# Power_MPU.net
KiCad netlist of a schematic drawn in Altium Designer
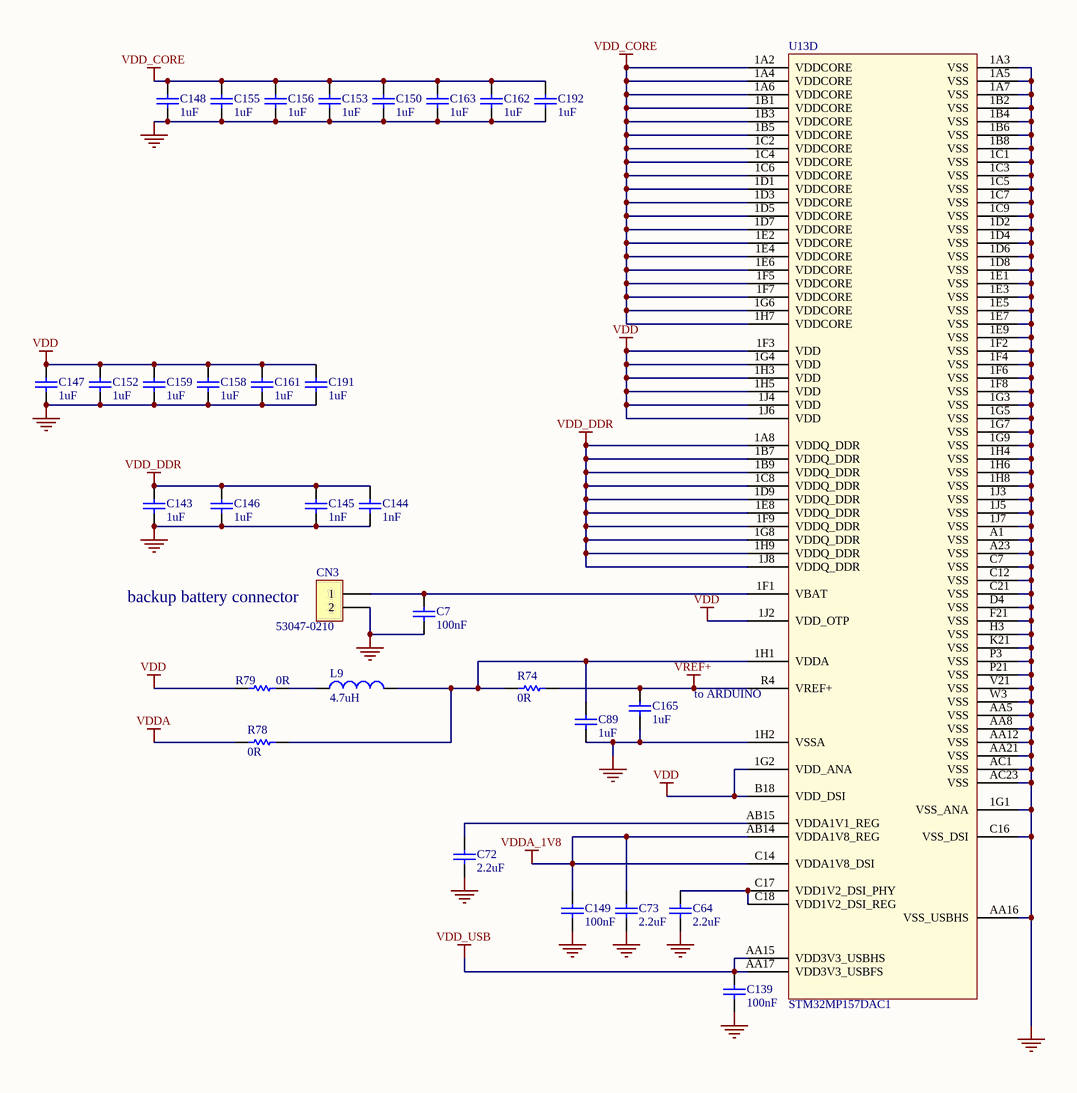
[diagram p0: Power_MPU.SchDoc]

(export (version "E")
  (design (tool "Eeschema 10.0.6"))
  (components
    (comp (ref "C7")
      (value "100nF")
      (footprint "C0402")
      (description "Capacitor,100nF,16V,X7R,10%,0402")
      (fields
        (field (name "INTERNAL_PART_NUMBER") "MCD-00006")
        (field (name "MANUFACTURER_PART_NUMBER") "CC0402KRX7R7BB104")
        (field (name "PROVIDED_BY") "SUBCO")
      )
      (libsource (lib "MCD_PARTS_database") (part "Capacitor"))
    )
    (comp (ref "C64")
      (value "2.2uF")
      (footprint "C0402")
      (description "Capacitor,MLCC,2.2uF,6V3,X5R,10%,0402,T=0.5")
      (fields
        (field (name "INTERNAL_PART_NUMBER") "MCD-01823")
        (field (name "MANUFACTURER_PART_NUMBER") "GRM155R60J225KE95D")
        (field (name "PROVIDED_BY") "SUBCO")
      )
      (libsource (lib "MCD_PARTS_database") (part "Capacitor"))
    )
    (comp (ref "C72")
      (value "2.2uF")
      (footprint "C0402")
      (description "Capacitor,MLCC,2.2uF,6V3,X5R,10%,0402,T=0.5")
      (fields
        (field (name "INTERNAL_PART_NUMBER") "MCD-01823")
        (field (name "MANUFACTURER_PART_NUMBER") "GRM155R60J225KE95D")
        (field (name "PROVIDED_BY") "SUBCO")
      )
      (libsource (lib "MCD_PARTS_database") (part "Capacitor"))
    )
    (comp (ref "C73")
      (value "2.2uF")
      (footprint "C0402")
      (description "Capacitor,MLCC,2.2uF,6V3,X5R,10%,0402,T=0.5")
      (fields
        (field (name "INTERNAL_PART_NUMBER") "MCD-01823")
        (field (name "MANUFACTURER_PART_NUMBER") "GRM155R60J225KE95D")
        (field (name "PROVIDED_BY") "SUBCO")
      )
      (libsource (lib "MCD_PARTS_database") (part "Capacitor"))
    )
    (comp (ref "C89")
      (value "1uF")
      (footprint "C0402")
      (description "Capacitor,1uF,6V3,X5R,10%,0402")
      (fields
        (field (name "INTERNAL_PART_NUMBER") "MCD-00095")
        (field (name "MANUFACTURER_PART_NUMBER") "GRM155R61E105KA12")
        (field (name "PROVIDED_BY") "SUBCO")
      )
      (libsource (lib "MCD_PARTS_database") (part "Capacitor"))
    )
    (comp (ref "C139")
      (value "100nF")
      (footprint "C0402")
      (description "Capacitor,100nF,16V,X7R,10%,0402")
      (fields
        (field (name "INTERNAL_PART_NUMBER") "MCD-00006")
        (field (name "MANUFACTURER_PART_NUMBER") "CC0402KRX7R7BB104")
        (field (name "PROVIDED_BY") "SUBCO")
      )
      (libsource (lib "MCD_PARTS_database") (part "Capacitor"))
    )
    (comp (ref "C143")
      (value "1uF")
      (footprint "C0402")
      (description "Capacitor,1uF,6V3,X5R,10%,0402")
      (fields
        (field (name "INTERNAL_PART_NUMBER") "MCD-00095")
        (field (name "MANUFACTURER_PART_NUMBER") "GRM155R61E105KA12")
        (field (name "PROVIDED_BY") "SUBCO")
      )
      (libsource (lib "MCD_PARTS_database") (part "Capacitor"))
    )
    (comp (ref "C144")
      (value "1nF")
      (footprint "C0402")
      (description "Capacitor,1nF,16V,X7R,10%,0402")
      (fields
        (field (name "INTERNAL_PART_NUMBER") "MCD-00198")
        (field (name "MANUFACTURER_PART_NUMBER") "CC0402KRX7R7BB102")
        (field (name "PROVIDED_BY") "SUBCO")
      )
      (libsource (lib "MCD_PARTS_database") (part "Capacitor"))
    )
    (comp (ref "C145")
      (value "1nF")
      (footprint "C0402")
      (description "Capacitor,1nF,16V,X7R,10%,0402")
      (fields
        (field (name "INTERNAL_PART_NUMBER") "MCD-00198")
        (field (name "MANUFACTURER_PART_NUMBER") "CC0402KRX7R7BB102")
        (field (name "PROVIDED_BY") "SUBCO")
      )
      (libsource (lib "MCD_PARTS_database") (part "Capacitor"))
    )
    (comp (ref "C146")
      (value "1uF")
      (footprint "C0402")
      (description "Capacitor,1uF,6V3,X5R,10%,0402")
      (fields
        (field (name "INTERNAL_PART_NUMBER") "MCD-00095")
        (field (name "MANUFACTURER_PART_NUMBER") "GRM155R61E105KA12")
        (field (name "PROVIDED_BY") "SUBCO")
      )
      (libsource (lib "MCD_PARTS_database") (part "Capacitor"))
    )
    (comp (ref "C147")
      (value "1uF")
      (footprint "C0402")
      (description "Capacitor,1uF,6V3,X5R,10%,0402")
      (fields
        (field (name "INTERNAL_PART_NUMBER") "MCD-00095")
        (field (name "MANUFACTURER_PART_NUMBER") "GRM155R61E105KA12")
        (field (name "PROVIDED_BY") "SUBCO")
      )
      (libsource (lib "MCD_PARTS_database") (part "Capacitor"))
    )
    (comp (ref "C148")
      (value "1uF")
      (footprint "C0402")
      (description "Capacitor,1uF,6V3,X5R,10%,0402")
      (fields
        (field (name "INTERNAL_PART_NUMBER") "MCD-00095")
        (field (name "MANUFACTURER_PART_NUMBER") "GRM155R61E105KA12")
        (field (name "PROVIDED_BY") "SUBCO")
      )
      (libsource (lib "MCD_PARTS_database") (part "Capacitor"))
    )
    (comp (ref "C149")
      (value "100nF")
      (footprint "C0402")
      (description "Capacitor,100nF,16V,X7R,10%,0402")
      (fields
        (field (name "INTERNAL_PART_NUMBER") "MCD-00006")
        (field (name "MANUFACTURER_PART_NUMBER") "CC0402KRX7R7BB104")
        (field (name "PROVIDED_BY") "SUBCO")
      )
      (libsource (lib "MCD_PARTS_database") (part "Capacitor"))
    )
    (comp (ref "C150")
      (value "1uF")
      (footprint "C0402")
      (description "Capacitor,1uF,6V3,X5R,10%,0402")
      (fields
        (field (name "INTERNAL_PART_NUMBER") "MCD-00095")
        (field (name "MANUFACTURER_PART_NUMBER") "GRM155R61E105KA12")
        (field (name "PROVIDED_BY") "SUBCO")
      )
      (libsource (lib "MCD_PARTS_database") (part "Capacitor"))
    )
    (comp (ref "C152")
      (value "1uF")
      (footprint "C0402")
      (description "Capacitor,1uF,6V3,X5R,10%,0402")
      (fields
        (field (name "INTERNAL_PART_NUMBER") "MCD-00095")
        (field (name "MANUFACTURER_PART_NUMBER") "GRM155R61E105KA12")
        (field (name "PROVIDED_BY") "SUBCO")
      )
      (libsource (lib "MCD_PARTS_database") (part "Capacitor"))
    )
    (comp (ref "C153")
      (value "1uF")
      (footprint "C0402")
      (description "Capacitor,1uF,6V3,X5R,10%,0402")
      (fields
        (field (name "INTERNAL_PART_NUMBER") "MCD-00095")
        (field (name "MANUFACTURER_PART_NUMBER") "GRM155R61E105KA12")
        (field (name "PROVIDED_BY") "SUBCO")
      )
      (libsource (lib "MCD_PARTS_database") (part "Capacitor"))
    )
    (comp (ref "C155")
      (value "1uF")
      (footprint "C0402")
      (description "Capacitor,1uF,6V3,X5R,10%,0402")
      (fields
        (field (name "INTERNAL_PART_NUMBER") "MCD-00095")
        (field (name "MANUFACTURER_PART_NUMBER") "GRM155R61E105KA12")
        (field (name "PROVIDED_BY") "SUBCO")
      )
      (libsource (lib "MCD_PARTS_database") (part "Capacitor"))
    )
    (comp (ref "C156")
      (value "1uF")
      (footprint "C0402")
      (description "Capacitor,1uF,6V3,X5R,10%,0402")
      (fields
        (field (name "INTERNAL_PART_NUMBER") "MCD-00095")
        (field (name "MANUFACTURER_PART_NUMBER") "GRM155R61E105KA12")
        (field (name "PROVIDED_BY") "SUBCO")
      )
      (libsource (lib "MCD_PARTS_database") (part "Capacitor"))
    )
    (comp (ref "C158")
      (value "1uF")
      (footprint "C0402")
      (description "Capacitor,1uF,6V3,X5R,10%,0402")
      (fields
        (field (name "INTERNAL_PART_NUMBER") "MCD-00095")
        (field (name "MANUFACTURER_PART_NUMBER") "GRM155R61E105KA12")
        (field (name "PROVIDED_BY") "SUBCO")
      )
      (libsource (lib "MCD_PARTS_database") (part "Capacitor"))
    )
    (comp (ref "C159")
      (value "1uF")
      (footprint "C0402")
      (description "Capacitor,1uF,6V3,X5R,10%,0402")
      (fields
        (field (name "INTERNAL_PART_NUMBER") "MCD-00095")
        (field (name "MANUFACTURER_PART_NUMBER") "GRM155R61E105KA12")
        (field (name "PROVIDED_BY") "SUBCO")
      )
      (libsource (lib "MCD_PARTS_database") (part "Capacitor"))
    )
    (comp (ref "C161")
      (value "1uF")
      (footprint "C0402")
      (description "Capacitor,1uF,6V3,X5R,10%,0402")
      (fields
        (field (name "INTERNAL_PART_NUMBER") "MCD-00095")
        (field (name "MANUFACTURER_PART_NUMBER") "GRM155R61E105KA12")
        (field (name "PROVIDED_BY") "SUBCO")
      )
      (libsource (lib "MCD_PARTS_database") (part "Capacitor"))
    )
    (comp (ref "C162")
      (value "1uF")
      (footprint "C0402")
      (description "Capacitor,1uF,6V3,X5R,10%,0402")
      (fields
        (field (name "INTERNAL_PART_NUMBER") "MCD-00095")
        (field (name "MANUFACTURER_PART_NUMBER") "GRM155R61E105KA12")
        (field (name "PROVIDED_BY") "SUBCO")
      )
      (libsource (lib "MCD_PARTS_database") (part "Capacitor"))
    )
    (comp (ref "C163")
      (value "1uF")
      (footprint "C0402")
      (description "Capacitor,1uF,6V3,X5R,10%,0402")
      (fields
        (field (name "INTERNAL_PART_NUMBER") "MCD-00095")
        (field (name "MANUFACTURER_PART_NUMBER") "GRM155R61E105KA12")
        (field (name "PROVIDED_BY") "SUBCO")
      )
      (libsource (lib "MCD_PARTS_database") (part "Capacitor"))
    )
    (comp (ref "C165")
      (value "1uF")
      (footprint "C0402")
      (description "Capacitor,1uF,6V3,X5R,10%,0402")
      (fields
        (field (name "INTERNAL_PART_NUMBER") "MCD-00095")
        (field (name "MANUFACTURER_PART_NUMBER") "GRM155R61E105KA12")
        (field (name "PROVIDED_BY") "SUBCO")
      )
      (libsource (lib "MCD_PARTS_database") (part "Capacitor"))
    )
    (comp (ref "C191")
      (value "1uF")
      (footprint "C0402")
      (description "Capacitor,1uF,6V3,X5R,10%,0402")
      (fields
        (field (name "INTERNAL_PART_NUMBER") "MCD-00095")
        (field (name "MANUFACTURER_PART_NUMBER") "GRM155R61E105KA12")
        (field (name "PROVIDED_BY") "SUBCO")
      )
      (libsource (lib "MCD_PARTS_database") (part "Capacitor"))
    )
    (comp (ref "C192")
      (value "1uF")
      (footprint "C0402")
      (description "Capacitor,1uF,6V3,X5R,10%,0402")
      (fields
        (field (name "INTERNAL_PART_NUMBER") "MCD-00095")
        (field (name "MANUFACTURER_PART_NUMBER") "GRM155R61E105KA12")
        (field (name "PROVIDED_BY") "SUBCO")
      )
      (libsource (lib "MCD_PARTS_database") (part "Capacitor"))
    )
    (comp (ref "CN3")
      (value "53047-0210")
      (footprint "CON_MOLEX_53047-0210")
      (description "Header 2 circuits, 1.25mm Pitch ,  Vertical, with Friction Lock")
      (fields
        (field (name "INTERNAL_PART_NUMBER") "MCD-00655")
        (field (name "MANUFACTURER") "MOLEX")
        (field (name "PROVIDED_BY") "SUBCO")
      )
      (libsource (lib "MCD_PARTS_database") (part "Header 2x1"))
    )
    (comp (ref "L9")
      (value "4.7uH")
      (footprint "L0603_H0P8")
      (description "Inductor, 4.7uH, +/-20%, 0.12A, 500mR, 0603, T=0.8mm")
      (fields (field (name "INTERNAL_PART_NUMBER") "MCD-03221") (field (name "MANUFACTURER") "TDK"))
      (libsource (lib "MCD_PARTS_database") (part "LQM18FN4R7M00D"))
    )
    (comp (ref "R74")
      (value "0R")
      (footprint "R0402")
      (description "Resistor,0R,0402,5%,1/16W")
      (fields
        (field (name "INTERNAL_PART_NUMBER") "MCD-00052")
        (field (name "MANUFACTURER_PART_NUMBER") "RC0402JR-070RL")
        (field (name "PROVIDED_BY") "SUBCO")
      )
      (libsource (lib "MCD_PARTS_database") (part "Resistor"))
    )
    (comp (ref "R78")
      (value "0R")
      (footprint "R0402")
      (description "Resistor,0R,0402,5%,1/16W")
      (fields
        (field (name "INTERNAL_PART_NUMBER") "MCD-00052")
        (field (name "MANUFACTURER_PART_NUMBER") "RC0402JR-070RL")
        (field (name "PROVIDED_BY") "SUBCO")
      )
      (libsource (lib "MCD_PARTS_database") (part "Resistor"))
    )
    (comp (ref "R79")
      (value "0R")
      (footprint "R0402")
      (description "Resistor,0R,0402,5%,1/16W")
      (fields
        (field (name "INTERNAL_PART_NUMBER") "MCD-00052")
        (field (name "MANUFACTURER_PART_NUMBER") "RC0402JR-070RL")
        (field (name "PROVIDED_BY") "SUBCO")
      )
      (libsource (lib "MCD_PARTS_database") (part "Resistor"))
    )
    (comp (ref "U13")
      (value "STM32MP157DAC1")
      (footprint "ICC_TFBGA361_12X12_STM32MP157CAC3_P050-065")
      (description "MPU TFBGA12x12 without crypto increased frequency")
      (fields
        (field (name "INTERNAL_PART_NUMBER") "MCD-02020")
        (field (name "MANUFACTURER") "STMICROELECTRONICS")
        (field (name "PROVIDED_BY") "SUBCO with ST control")
      )
      (libsource (lib "MCD_PARTS_database") (part "STM32MP157DAC1"))
    )
  )
  (nets
    (net (code "1") (name "GND") (class "Default")
      (node (ref "C139") (pin "1") (pinfunction "1_1") (pintype "passive"))
      (node (ref "C143") (pin "1") (pinfunction "1_1") (pintype "passive"))
      (node (ref "C144") (pin "1") (pinfunction "1_1") (pintype "passive"))
      (node (ref "C145") (pin "1") (pinfunction "1_1") (pintype "passive"))
      (node (ref "C146") (pin "1") (pinfunction "1_1") (pintype "passive"))
      (node (ref "C147") (pin "1") (pinfunction "1_1") (pintype "passive"))
      (node (ref "C148") (pin "1") (pinfunction "1_1") (pintype "passive"))
      (node (ref "C149") (pin "1") (pinfunction "1_1") (pintype "passive"))
      (node (ref "C150") (pin "1") (pinfunction "1_1") (pintype "passive"))
      (node (ref "C152") (pin "1") (pinfunction "1_1") (pintype "passive"))
      (node (ref "C153") (pin "1") (pinfunction "1_1") (pintype "passive"))
      (node (ref "C155") (pin "1") (pinfunction "1_1") (pintype "passive"))
      (node (ref "C156") (pin "1") (pinfunction "1_1") (pintype "passive"))
      (node (ref "C158") (pin "1") (pinfunction "1_1") (pintype "passive"))
      (node (ref "C159") (pin "1") (pinfunction "1_1") (pintype "passive"))
      (node (ref "C161") (pin "1") (pinfunction "1_1") (pintype "passive"))
      (node (ref "C162") (pin "1") (pinfunction "1_1") (pintype "passive"))
      (node (ref "C163") (pin "1") (pinfunction "1_1") (pintype "passive"))
      (node (ref "C165") (pin "1") (pinfunction "1_1") (pintype "passive"))
      (node (ref "C191") (pin "1") (pinfunction "1_1") (pintype "passive"))
      (node (ref "C192") (pin "1") (pinfunction "1_1") (pintype "passive"))
      (node (ref "C64") (pin "2") (pinfunction "2_2") (pintype "passive"))
      (node (ref "C7") (pin "1") (pinfunction "1_1") (pintype "passive"))
      (node (ref "C72") (pin "2") (pinfunction "2_2") (pintype "passive"))
      (node (ref "C73") (pin "2") (pinfunction "2_2") (pintype "passive"))
      (node (ref "C89") (pin "1") (pinfunction "1_1") (pintype "passive"))
      (node (ref "CN3") (pin "2") (pinfunction "2_2") (pintype "passive"))
      (node (ref "U13") (pin "1A3") (pinfunction "VSS_1A3") (pintype "passive"))
      (node (ref "U13") (pin "1A5") (pinfunction "VSS_1A5") (pintype "passive"))
      (node (ref "U13") (pin "1A7") (pinfunction "VSS_1A7") (pintype "passive"))
      (node (ref "U13") (pin "1B2") (pinfunction "VSS_1B2") (pintype "passive"))
      (node (ref "U13") (pin "1B4") (pinfunction "VSS_1B4") (pintype "passive"))
      (node (ref "U13") (pin "1B6") (pinfunction "VSS_1B6") (pintype "passive"))
      (node (ref "U13") (pin "1B8") (pinfunction "VSS_1B8") (pintype "passive"))
      (node (ref "U13") (pin "1C1") (pinfunction "VSS_1C1") (pintype "passive"))
      (node (ref "U13") (pin "1C3") (pinfunction "VSS_1C3") (pintype "passive"))
      (node (ref "U13") (pin "1C5") (pinfunction "VSS_1C5") (pintype "passive"))
      (node (ref "U13") (pin "1C7") (pinfunction "VSS_1C7") (pintype "passive"))
      (node (ref "U13") (pin "1C9") (pinfunction "VSS_1C9") (pintype "passive"))
      (node (ref "U13") (pin "1D2") (pinfunction "VSS_1D2") (pintype "passive"))
      (node (ref "U13") (pin "1D4") (pinfunction "VSS_1D4") (pintype "passive"))
      (node (ref "U13") (pin "1D6") (pinfunction "VSS_1D6") (pintype "passive"))
      (node (ref "U13") (pin "1D8") (pinfunction "VSS_1D8") (pintype "passive"))
      (node (ref "U13") (pin "1E1") (pinfunction "VSS_1E1") (pintype "passive"))
      (node (ref "U13") (pin "1E3") (pinfunction "VSS_1E3") (pintype "passive"))
      (node (ref "U13") (pin "1E5") (pinfunction "VSS_1E5") (pintype "passive"))
      (node (ref "U13") (pin "1E7") (pinfunction "VSS_1E7") (pintype "passive"))
      (node (ref "U13") (pin "1E9") (pinfunction "VSS_1E9") (pintype "passive"))
      (node (ref "U13") (pin "1F2") (pinfunction "VSS_1F2") (pintype "passive"))
      (node (ref "U13") (pin "1F4") (pinfunction "VSS_1F4") (pintype "passive"))
      (node (ref "U13") (pin "1F6") (pinfunction "VSS_1F6") (pintype "passive"))
      (node (ref "U13") (pin "1F8") (pinfunction "VSS_1F8") (pintype "passive"))
      (node (ref "U13") (pin "1G1") (pinfunction "VSS_ANA_1G1") (pintype "passive"))
      (node (ref "U13") (pin "1G3") (pinfunction "VSS_1G3") (pintype "passive"))
      (node (ref "U13") (pin "1G5") (pinfunction "VSS_1G5") (pintype "passive"))
      (node (ref "U13") (pin "1G7") (pinfunction "VSS_1G7") (pintype "passive"))
      (node (ref "U13") (pin "1G9") (pinfunction "VSS_1G9") (pintype "passive"))
      (node (ref "U13") (pin "1H2") (pinfunction "VSSA_1H2") (pintype "passive"))
      (node (ref "U13") (pin "1H4") (pinfunction "VSS_1H4") (pintype "passive"))
      (node (ref "U13") (pin "1H6") (pinfunction "VSS_1H6") (pintype "passive"))
      (node (ref "U13") (pin "1H8") (pinfunction "VSS_1H8") (pintype "passive"))
      (node (ref "U13") (pin "1J3") (pinfunction "VSS_1J3") (pintype "passive"))
      (node (ref "U13") (pin "1J5") (pinfunction "VSS_1J5") (pintype "passive"))
      (node (ref "U13") (pin "1J7") (pinfunction "VSS_1J7") (pintype "passive"))
      (node (ref "U13") (pin "A1") (pinfunction "VSS_A1") (pintype "passive"))
      (node (ref "U13") (pin "A23") (pinfunction "VSS_A23") (pintype "passive"))
      (node (ref "U13") (pin "AA12") (pinfunction "VSS_AA12") (pintype "passive"))
      (node (ref "U13") (pin "AA16") (pinfunction "VSS_USBHS_AA16") (pintype "passive"))
      (node (ref "U13") (pin "AA21") (pinfunction "VSS_AA21") (pintype "passive"))
      (node (ref "U13") (pin "AA5") (pinfunction "VSS_AA5") (pintype "passive"))
      (node (ref "U13") (pin "AA8") (pinfunction "VSS_AA8") (pintype "passive"))
      (node (ref "U13") (pin "AC1") (pinfunction "VSS_AC1") (pintype "passive"))
      (node (ref "U13") (pin "AC23") (pinfunction "VSS_AC23") (pintype "passive"))
      (node (ref "U13") (pin "C12") (pinfunction "VSS_C12") (pintype "passive"))
      (node (ref "U13") (pin "C16") (pinfunction "VSS_DSI_C16") (pintype "passive"))
      (node (ref "U13") (pin "C21") (pinfunction "VSS_C21") (pintype "passive"))
      (node (ref "U13") (pin "C7") (pinfunction "VSS_C7") (pintype "passive"))
      (node (ref "U13") (pin "D4") (pinfunction "VSS_D4") (pintype "passive"))
      (node (ref "U13") (pin "F21") (pinfunction "VSS_F21") (pintype "passive"))
      (node (ref "U13") (pin "H3") (pinfunction "VSS_H3") (pintype "passive"))
      (node (ref "U13") (pin "K21") (pinfunction "VSS_K21") (pintype "passive"))
      (node (ref "U13") (pin "P21") (pinfunction "VSS_P21") (pintype "passive"))
      (node (ref "U13") (pin "P3") (pinfunction "VSS_P3") (pintype "passive"))
      (node (ref "U13") (pin "V21") (pinfunction "VSS_V21") (pintype "passive"))
      (node (ref "U13") (pin "W3") (pinfunction "VSS_W3") (pintype "passive"))
    )
    (net (code "2") (name "Net-(L9-Pad1)") (class "Default")
      (node (ref "L9") (pin "1") (pinfunction "1_1") (pintype "passive"))
      (node (ref "R79") (pin "2") (pinfunction "2_2") (pintype "passive"))
    )
    (net (code "3") (name "Net-(U13D-VBAT)") (class "Default")
      (node (ref "C7") (pin "2") (pinfunction "2_2") (pintype "passive"))
      (node (ref "CN3") (pin "1") (pinfunction "1_1") (pintype "passive"))
      (node (ref "U13") (pin "1F1") (pinfunction "VBAT_1F1") (pintype "passive"))
    )
    (net (code "4") (name "Net-(U13D-VDD1V2_DSI_PHY)") (class "Default")
      (node (ref "C64") (pin "1") (pinfunction "1_1") (pintype "passive"))
      (node (ref "U13") (pin "C17") (pinfunction "VDD1V2_DSI_PHY_C17") (pintype "passive"))
      (node (ref "U13") (pin "C18") (pinfunction "VDD1V2_DSI_REG_C18") (pintype "passive"))
    )
    (net (code "5") (name "Net-(U13D-VDDA)") (class "Default")
      (node (ref "C89") (pin "2") (pinfunction "2_2") (pintype "passive"))
      (node (ref "L9") (pin "2") (pinfunction "2_2") (pintype "passive"))
      (node (ref "R74") (pin "1") (pinfunction "1_1") (pintype "passive"))
      (node (ref "R78") (pin "2") (pinfunction "2_2") (pintype "passive"))
      (node (ref "U13") (pin "1H1") (pinfunction "VDDA_1H1") (pintype "passive"))
    )
    (net (code "6") (name "Net-(U13D-VDDA1V1_REG)") (class "Default")
      (node (ref "C72") (pin "1") (pinfunction "1_1") (pintype "passive"))
      (node (ref "U13") (pin "AB15") (pinfunction "VDDA1V1_REG_AB15") (pintype "passive"))
    )
    (net (code "7") (name "VDD") (class "Default")
      (node (ref "C147") (pin "2") (pinfunction "2_2") (pintype "passive"))
      (node (ref "C152") (pin "2") (pinfunction "2_2") (pintype "passive"))
      (node (ref "C158") (pin "2") (pinfunction "2_2") (pintype "passive"))
      (node (ref "C159") (pin "2") (pinfunction "2_2") (pintype "passive"))
      (node (ref "C161") (pin "2") (pinfunction "2_2") (pintype "passive"))
      (node (ref "C191") (pin "2") (pinfunction "2_2") (pintype "passive"))
      (node (ref "R79") (pin "1") (pinfunction "1_1") (pintype "passive"))
      (node (ref "U13") (pin "1F3") (pinfunction "VDD_1F3") (pintype "passive"))
      (node (ref "U13") (pin "1G2") (pinfunction "VDD_ANA_1G2") (pintype "passive"))
      (node (ref "U13") (pin "1G4") (pinfunction "VDD_1G4") (pintype "passive"))
      (node (ref "U13") (pin "1H3") (pinfunction "VDD_1H3") (pintype "passive"))
      (node (ref "U13") (pin "1H5") (pinfunction "VDD_1H5") (pintype "passive"))
      (node (ref "U13") (pin "1J2") (pinfunction "VDD_OTP_1J2") (pintype "passive"))
      (node (ref "U13") (pin "1J4") (pinfunction "VDD_1J4") (pintype "passive"))
      (node (ref "U13") (pin "1J6") (pinfunction "VDD_1J6") (pintype "passive"))
      (node (ref "U13") (pin "B18") (pinfunction "VDD_DSI_B18") (pintype "passive"))
    )
    (net (code "8") (name "VDDA") (class "Default")
      (node (ref "R78") (pin "1") (pinfunction "1_1") (pintype "passive"))
    )
    (net (code "9") (name "VDDA_1V8") (class "Default")
      (node (ref "C149") (pin "2") (pinfunction "2_2") (pintype "passive"))
      (node (ref "C73") (pin "1") (pinfunction "1_1") (pintype "passive"))
      (node (ref "U13") (pin "AB14") (pinfunction "VDDA1V8_REG_AB14") (pintype "passive"))
      (node (ref "U13") (pin "C14") (pinfunction "VDDA1V8_DSI_C14") (pintype "passive"))
    )
    (net (code "10") (name "VDD_CORE") (class "Default")
      (node (ref "C148") (pin "2") (pinfunction "2_2") (pintype "passive"))
      (node (ref "C150") (pin "2") (pinfunction "2_2") (pintype "passive"))
      (node (ref "C153") (pin "2") (pinfunction "2_2") (pintype "passive"))
      (node (ref "C155") (pin "2") (pinfunction "2_2") (pintype "passive"))
      (node (ref "C156") (pin "2") (pinfunction "2_2") (pintype "passive"))
      (node (ref "C162") (pin "2") (pinfunction "2_2") (pintype "passive"))
      (node (ref "C163") (pin "2") (pinfunction "2_2") (pintype "passive"))
      (node (ref "C192") (pin "2") (pinfunction "2_2") (pintype "passive"))
      (node (ref "U13") (pin "1A2") (pinfunction "VDDCORE_1A2") (pintype "passive"))
      (node (ref "U13") (pin "1A4") (pinfunction "VDDCORE_1A4") (pintype "passive"))
      (node (ref "U13") (pin "1A6") (pinfunction "VDDCORE_1A6") (pintype "passive"))
      (node (ref "U13") (pin "1B1") (pinfunction "VDDCORE_1B1") (pintype "passive"))
      (node (ref "U13") (pin "1B3") (pinfunction "VDDCORE_1B3") (pintype "passive"))
      (node (ref "U13") (pin "1B5") (pinfunction "VDDCORE_1B5") (pintype "passive"))
      (node (ref "U13") (pin "1C2") (pinfunction "VDDCORE_1C2") (pintype "passive"))
      (node (ref "U13") (pin "1C4") (pinfunction "VDDCORE_1C4") (pintype "passive"))
      (node (ref "U13") (pin "1C6") (pinfunction "VDDCORE_1C6") (pintype "passive"))
      (node (ref "U13") (pin "1D1") (pinfunction "VDDCORE_1D1") (pintype "passive"))
      (node (ref "U13") (pin "1D3") (pinfunction "VDDCORE_1D3") (pintype "passive"))
      (node (ref "U13") (pin "1D5") (pinfunction "VDDCORE_1D5") (pintype "passive"))
      (node (ref "U13") (pin "1D7") (pinfunction "VDDCORE_1D7") (pintype "passive"))
      (node (ref "U13") (pin "1E2") (pinfunction "VDDCORE_1E2") (pintype "passive"))
      (node (ref "U13") (pin "1E4") (pinfunction "VDDCORE_1E4") (pintype "passive"))
      (node (ref "U13") (pin "1E6") (pinfunction "VDDCORE_1E6") (pintype "passive"))
      (node (ref "U13") (pin "1F5") (pinfunction "VDDCORE_1F5") (pintype "passive"))
      (node (ref "U13") (pin "1F7") (pinfunction "VDDCORE_1F7") (pintype "passive"))
      (node (ref "U13") (pin "1G6") (pinfunction "VDDCORE_1G6") (pintype "passive"))
      (node (ref "U13") (pin "1H7") (pinfunction "VDDCORE_1H7") (pintype "passive"))
    )
    (net (code "11") (name "VDD_DDR") (class "Default")
      (node (ref "C143") (pin "2") (pinfunction "2_2") (pintype "passive"))
      (node (ref "C144") (pin "2") (pinfunction "2_2") (pintype "passive"))
      (node (ref "C145") (pin "2") (pinfunction "2_2") (pintype "passive"))
      (node (ref "C146") (pin "2") (pinfunction "2_2") (pintype "passive"))
      (node (ref "U13") (pin "1A8") (pinfunction "VDDQ_DDR_1A8") (pintype "passive"))
      (node (ref "U13") (pin "1B7") (pinfunction "VDDQ_DDR_1B7") (pintype "passive"))
      (node (ref "U13") (pin "1B9") (pinfunction "VDDQ_DDR_1B9") (pintype "passive"))
      (node (ref "U13") (pin "1C8") (pinfunction "VDDQ_DDR_1C8") (pintype "passive"))
      (node (ref "U13") (pin "1D9") (pinfunction "VDDQ_DDR_1D9") (pintype "passive"))
      (node (ref "U13") (pin "1E8") (pinfunction "VDDQ_DDR_1E8") (pintype "passive"))
      (node (ref "U13") (pin "1F9") (pinfunction "VDDQ_DDR_1F9") (pintype "passive"))
      (node (ref "U13") (pin "1G8") (pinfunction "VDDQ_DDR_1G8") (pintype "passive"))
      (node (ref "U13") (pin "1H9") (pinfunction "VDDQ_DDR_1H9") (pintype "passive"))
      (node (ref "U13") (pin "1J8") (pinfunction "VDDQ_DDR_1J8") (pintype "passive"))
    )
    (net (code "12") (name "VDD_USB") (class "Default")
      (node (ref "C139") (pin "2") (pinfunction "2_2") (pintype "passive"))
      (node (ref "U13") (pin "AA15") (pinfunction "VDD3V3_USBHS_AA15") (pintype "passive"))
      (node (ref "U13") (pin "AA17") (pinfunction "VDD3V3_USBFS_AA17") (pintype "passive"))
    )
    (net (code "13") (name "VREF+") (class "Default")
      (node (ref "C165") (pin "2") (pinfunction "2_2") (pintype "passive"))
      (node (ref "R74") (pin "2") (pinfunction "2_2") (pintype "passive"))
      (node (ref "U13") (pin "R4") (pinfunction "VREF+_R4") (pintype "passive"))
    )
  )
)
